# Schematic_skinBot_tether_wire_board_v1.net
KiCad netlist of a schematic drawn in Altium Designer
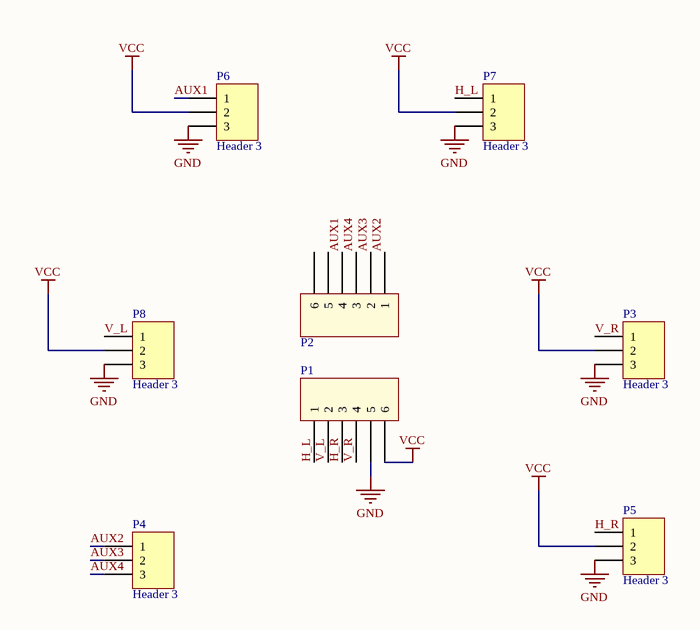
[diagram p0: Schematic_skinBot_tether_wire_board_v1.SchDoc]

(export (version "E")
  (design (tool "Eeschema 10.0.6"))
  (components
    (comp (ref "P1")
      (value "JST SH 6")
      (footprint "JST SH 6 TOP ENTRY 1MM")
      (fields (field (name "SPARKFUN PART NUMBER") "PRT-10210"))
      (libsource (lib "") (part "JST SH 6_1"))
    )
    (comp (ref "P2")
      (value "JST SH 6")
      (footprint "JST SH 6 TOP ENTRY 1MM")
      (fields (field (name "SPARKFUN PART NUMBER") "PRT-10210"))
      (libsource (lib "Artem_Library") (part "JST SH 6"))
    )
    (comp (ref "P3")
      (value "Header 3")
      (footprint "HDR1X3")
      (description "Header, 3-Pin")
      (fields (field (name "PUBLISHER") "Altium Limited"))
      (libsource (lib "Miscellaneous Connectors") (part "Header 3"))
    )
    (comp (ref "P4")
      (value "Header 3")
      (footprint "HDR1X3")
      (description "Header, 3-Pin")
      (fields (field (name "PUBLISHER") "Altium Limited"))
      (libsource (lib "Miscellaneous Connectors") (part "Header 3"))
    )
    (comp (ref "P5")
      (value "Header 3")
      (footprint "HDR1X3")
      (description "Header, 3-Pin")
      (fields (field (name "PUBLISHER") "Altium Limited"))
      (libsource (lib "Miscellaneous Connectors") (part "Header 3"))
    )
    (comp (ref "P6")
      (value "Header 3")
      (footprint "HDR1X3")
      (description "Header, 3-Pin")
      (fields (field (name "PUBLISHER") "Altium Limited"))
      (libsource (lib "Miscellaneous Connectors") (part "Header 3"))
    )
    (comp (ref "P7")
      (value "Header 3")
      (footprint "HDR1X3")
      (description "Header, 3-Pin")
      (fields (field (name "PUBLISHER") "Altium Limited"))
      (libsource (lib "Miscellaneous Connectors") (part "Header 3"))
    )
    (comp (ref "P8")
      (value "Header 3")
      (footprint "HDR1X3")
      (description "Header, 3-Pin")
      (fields (field (name "PUBLISHER") "Altium Limited"))
      (libsource (lib "Miscellaneous Connectors") (part "Header 3"))
    )
  )
  (nets
    (net (code "1") (name "/AUX1") (class "Default")
      (node (ref "P2") (pin "4") (pinfunction "4_4") (pintype "passive"))
      (node (ref "P6") (pin "1") (pinfunction "1_1") (pintype "passive"))
    )
    (net (code "2") (name "/AUX2") (class "Default")
      (node (ref "P2") (pin "1") (pinfunction "1_1") (pintype "passive"))
      (node (ref "P4") (pin "1") (pinfunction "1_1") (pintype "passive"))
    )
    (net (code "3") (name "/AUX3") (class "Default")
      (node (ref "P2") (pin "2") (pinfunction "2_2") (pintype "passive"))
      (node (ref "P4") (pin "2") (pinfunction "2_2") (pintype "passive"))
    )
    (net (code "4") (name "/AUX4") (class "Default")
      (node (ref "P2") (pin "3") (pinfunction "3_3") (pintype "passive"))
      (node (ref "P4") (pin "3") (pinfunction "3_3") (pintype "passive"))
    )
    (net (code "5") (name "/H_L") (class "Default")
      (node (ref "P1") (pin "1") (pinfunction "1_1") (pintype "passive"))
      (node (ref "P7") (pin "1") (pinfunction "1_1") (pintype "passive"))
    )
    (net (code "6") (name "/H_R") (class "Default")
      (node (ref "P1") (pin "3") (pinfunction "3_3") (pintype "passive"))
      (node (ref "P5") (pin "1") (pinfunction "1_1") (pintype "passive"))
    )
    (net (code "7") (name "/V_L") (class "Default")
      (node (ref "P1") (pin "2") (pinfunction "2_2") (pintype "passive"))
      (node (ref "P8") (pin "1") (pinfunction "1_1") (pintype "passive"))
    )
    (net (code "8") (name "/V_R") (class "Default")
      (node (ref "P1") (pin "4") (pinfunction "4_4") (pintype "passive"))
      (node (ref "P3") (pin "1") (pinfunction "1_1") (pintype "passive"))
    )
    (net (code "9") (name "GND") (class "Default")
      (node (ref "P1") (pin "5") (pinfunction "5_5") (pintype "passive"))
      (node (ref "P3") (pin "3") (pinfunction "3_3") (pintype "passive"))
      (node (ref "P5") (pin "3") (pinfunction "3_3") (pintype "passive"))
      (node (ref "P6") (pin "3") (pinfunction "3_3") (pintype "passive"))
      (node (ref "P7") (pin "3") (pinfunction "3_3") (pintype "passive"))
      (node (ref "P8") (pin "3") (pinfunction "3_3") (pintype "passive"))
    )
    (net (code "10") (name "VCC") (class "Default")
      (node (ref "P1") (pin "6") (pinfunction "6_6") (pintype "passive"))
      (node (ref "P3") (pin "2") (pinfunction "2_2") (pintype "passive"))
      (node (ref "P5") (pin "2") (pinfunction "2_2") (pintype "passive"))
      (node (ref "P6") (pin "2") (pinfunction "2_2") (pintype "passive"))
      (node (ref "P7") (pin "2") (pinfunction "2_2") (pintype "passive"))
      (node (ref "P8") (pin "2") (pinfunction "2_2") (pintype "passive"))
    )
    (net (code "11") (name "unconnected-(P2-Pad5)") (class "Default")
      (node (ref "P2") (pin "5") (pinfunction "5_5") (pintype "passive"))
    )
    (net (code "12") (name "unconnected-(P2-Pad6)") (class "Default")
      (node (ref "P2") (pin "6") (pinfunction "6_6") (pintype "passive"))
    )
  )
)
